# smart_mask_v_2_0.net
KiCad netlist of a schematic drawn in Altium Designer
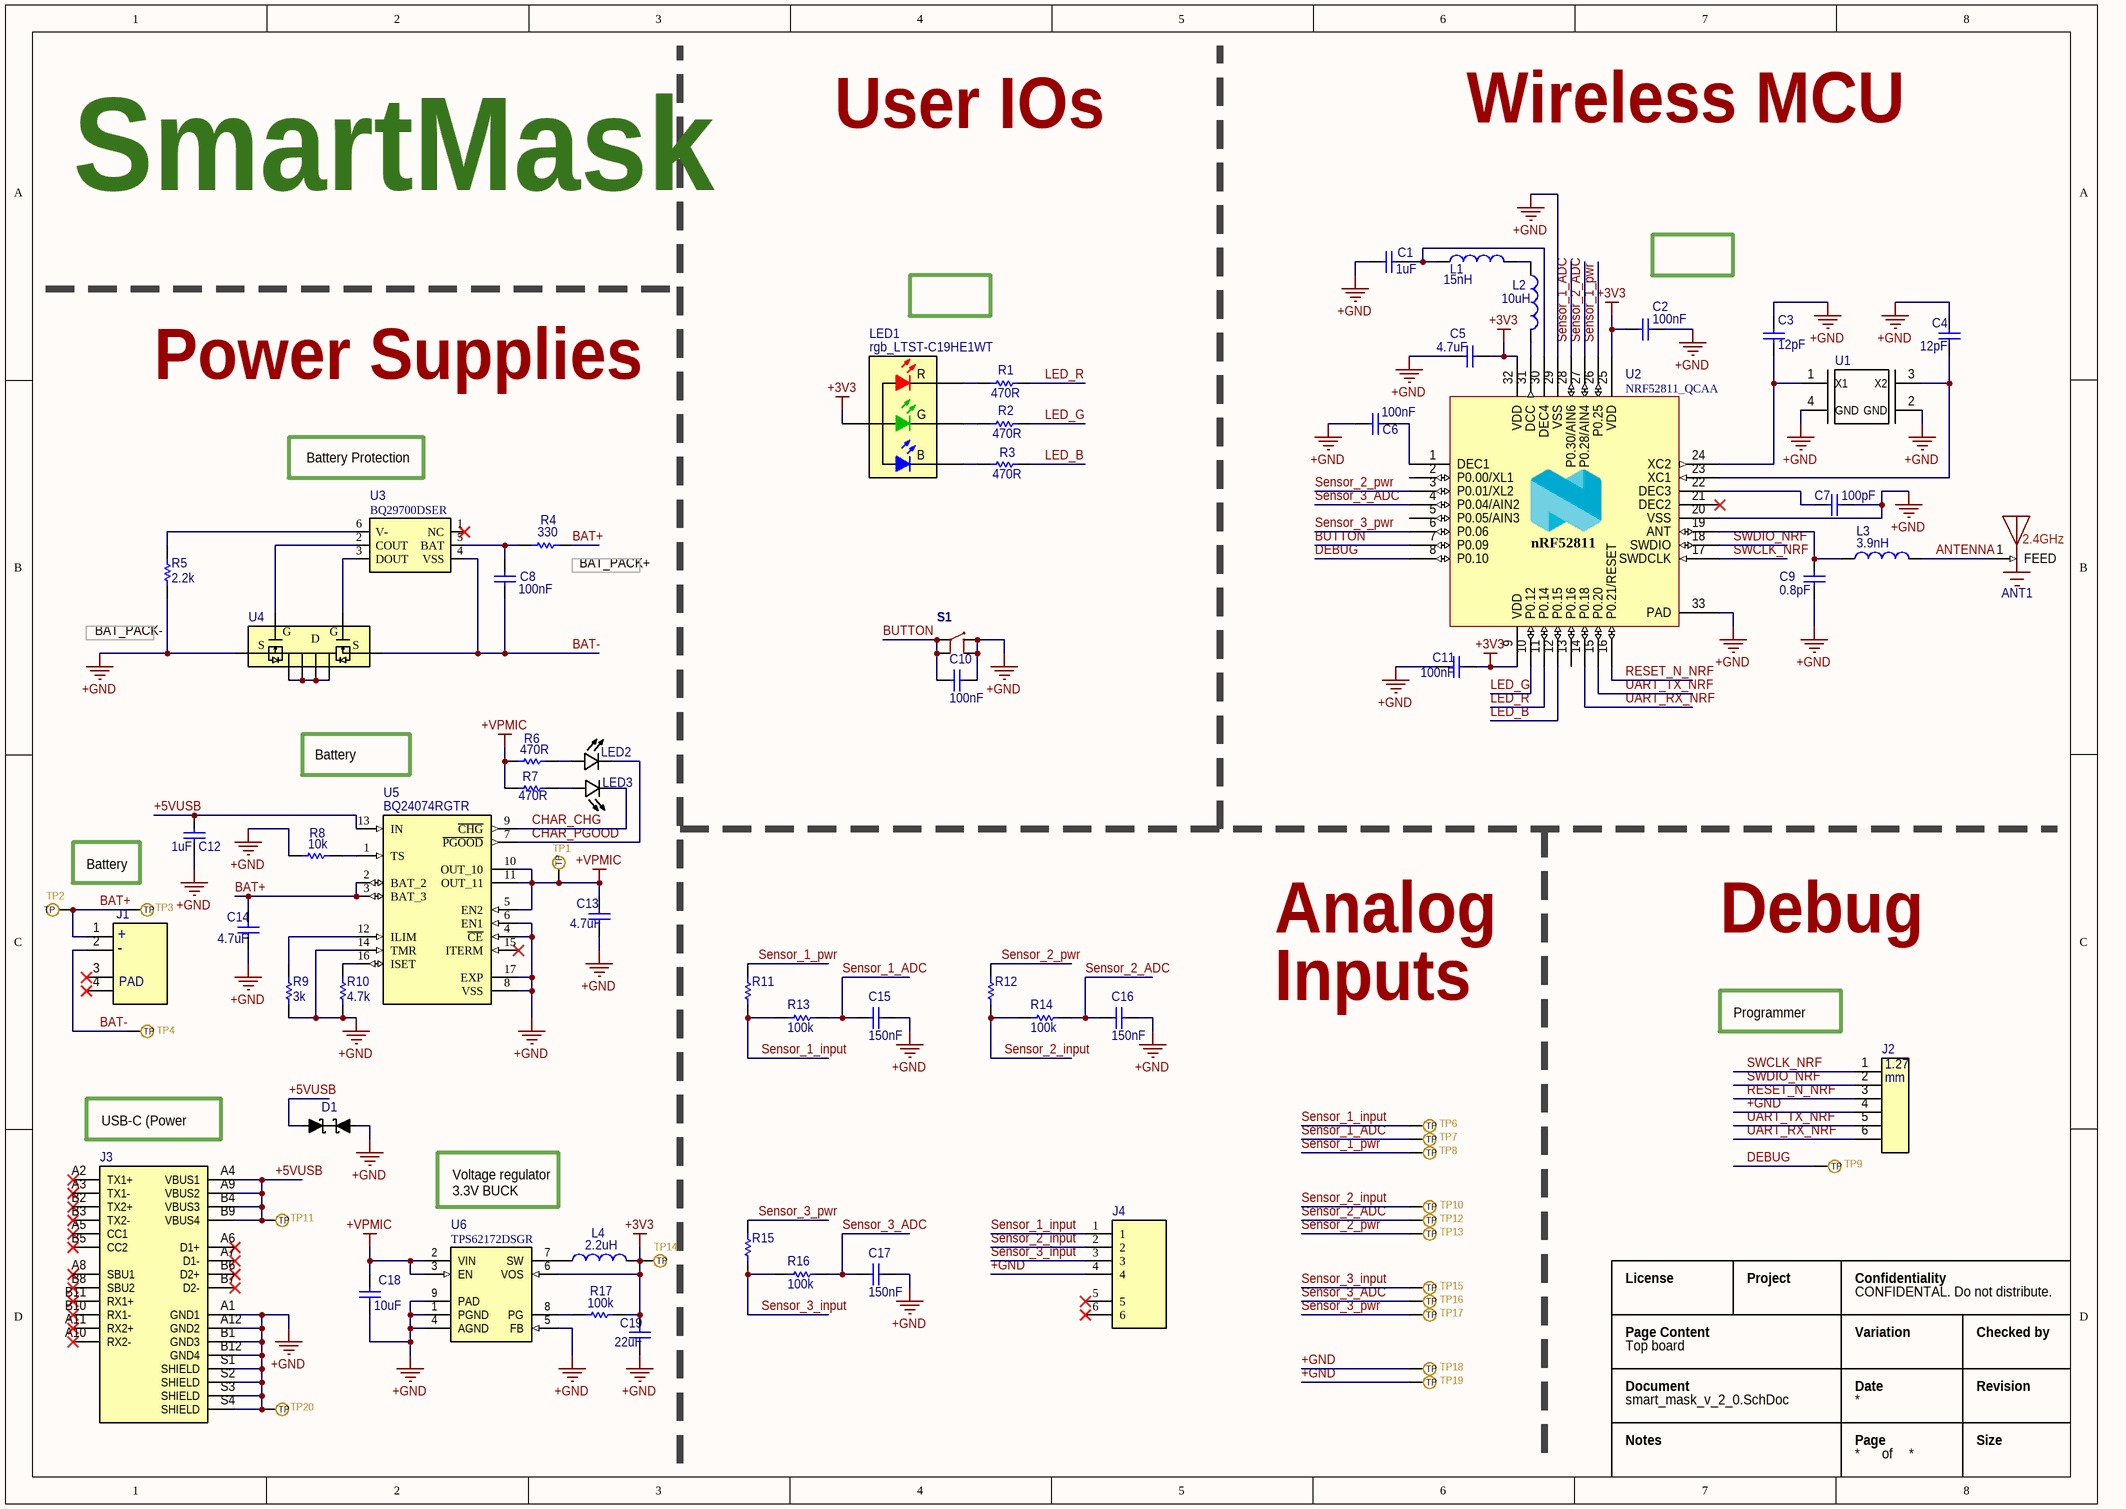
[diagram p0: smart_mask_v_2_0.SchDoc]

(export (version "E")
  (design (tool "Eeschema 10.0.6"))
  (components
    (comp (ref "ANT1")
      (value "2450AT43F0100E")
      (footprint "ANT_2450AT43F0100E")
      (description "RF ANT 2.4GHZ CHIP SOLDER SMD")
      (fields (field (name "MANUFACTURER") "Johanson Technology Inc."))
      (libsource (lib "chips") (part "2450AT43F0100E"))
    )
    (comp (ref "C1")
      (value "1uF")
      (footprint "C0603")
      (description "CAP CER 1UF 10V X5R 0603")
      (fields
        (field (name "MANUFACTURER PART NUMBER") "CL10A105KP8NNNC")
        (field (name "MANUFACTURER") "Samsung Electro-Mechanics")
      )
      (libsource (lib "rcl") (part "CAP 1uF 0603"))
    )
    (comp (ref "C2")
      (value "100nF")
      (footprint "C0402")
      (description "CAP CER 0.1UF 16V X7R 0402")
      (fields
        (field (name "MANUFACTURER PART NUMBER") "GRM155R71C104KA88J")
        (field (name "MANUFACTURER") "Murata Electronics")
      )
      (libsource (lib "rcl") (part "CAP 100nF 0402"))
    )
    (comp (ref "C3")
      (value "12pF")
      (footprint "C0402")
      (description "CAP CER 12PF 50V C0G/NP0 0402")
      (fields
        (field (name "MANUFACTURER PART NUMBER") "GRM1555C1H120JA01J")
        (field (name "MANUFACTURER") "Murata Electronics")
      )
      (libsource (lib "rcl") (part "CAP 12pF 0402"))
    )
    (comp (ref "C4")
      (value "12pF")
      (footprint "C0402")
      (description "CAP CER 12PF 50V C0G/NP0 0402")
      (fields
        (field (name "MANUFACTURER PART NUMBER") "GRM1555C1H120JA01J")
        (field (name "MANUFACTURER") "Murata Electronics")
      )
      (libsource (lib "rcl") (part "CAP 12pF 0402"))
    )
    (comp (ref "C5")
      (value "4.7uF")
      (footprint "C0603")
      (description "CAP CER 4.7UF 10V X5R 0603")
      (fields
        (field (name "MANUFACTURER PART NUMBER") "CL10A475KP8NNNC")
        (field (name "MANUFACTURER") "Samsung Electro-Mechanics")
      )
      (libsource (lib "rcl") (part "CAP 4.7uF 0603"))
    )
    (comp (ref "C6")
      (value "100nF")
      (footprint "C0402")
      (description "CAP CER 0.1UF 16V X7R 0402")
      (fields
        (field (name "MANUFACTURER PART NUMBER") "GRM155R71C104KA88J")
        (field (name "MANUFACTURER") "Murata Electronics")
      )
      (libsource (lib "rcl") (part "CAP 100nF 0402"))
    )
    (comp (ref "C7")
      (value "100pF")
      (footprint "C0402")
      (description "CAP CER 100PF 50V C0G/NP0 0402")
      (fields
        (field (name "MANUFACTURER PART NUMBER") "GRM1555C1H101JA01J")
        (field (name "MANUFACTURER") "Murata Electronics")
      )
      (libsource (lib "rcl") (part "CAP 100pF 0402"))
    )
    (comp (ref "C8")
      (value "100nF")
      (footprint "C0402")
      (description "CAP CER 0.1UF 16V X7R 0402")
      (fields
        (field (name "MANUFACTURER PART NUMBER") "GRM155R71C104KA88J")
        (field (name "MANUFACTURER") "Murata Electronics")
      )
      (libsource (lib "rcl") (part "CAP 100nF 0402"))
    )
    (comp (ref "C9")
      (value "0.8pF")
      (footprint "C0402")
      (description "CAP CER 0.8PF 50V C0G/NP0 0402")
      (fields
        (field (name "MANUFACTURER PART NUMBER") "GRM1555C1HR80BA01J")
        (field (name "MANUFACTURER") "Murata Electronics")
      )
      (libsource (lib "rcl") (part "CAP 0.8pF 0402"))
    )
    (comp (ref "C10")
      (value "100nF")
      (footprint "C0402")
      (description "CAP CER 0.1UF 16V X7R 0402")
      (fields
        (field (name "MANUFACTURER PART NUMBER") "GRM155R71C104KA88J")
        (field (name "MANUFACTURER") "Murata Electronics")
      )
      (libsource (lib "rcl") (part "CAP 100nF 0402"))
    )
    (comp (ref "C11")
      (value "100nF")
      (footprint "C0402")
      (description "CAP CER 0.1UF 16V X7R 0402")
      (fields
        (field (name "MANUFACTURER PART NUMBER") "GRM155R71C104KA88J")
        (field (name "MANUFACTURER") "Murata Electronics")
      )
      (libsource (lib "rcl") (part "CAP 100nF 0402"))
    )
    (comp (ref "C12")
      (value "1uF")
      (footprint "C0402")
      (description "CAP CER 1UF 10V X6S 0402")
      (fields
        (field (name "MANUFACTURER PART NUMBER") "GRM155C81A105KA12D")
        (field (name "MANUFACTURER") "Murata Electronics")
      )
      (libsource (lib "rcl") (part "CAP 1uF 0402"))
    )
    (comp (ref "C13")
      (value "4.7uF")
      (footprint "C0402")
      (description "CAP CER 4.7UF 6.3V X5R 0402")
      (fields
        (field (name "MANUFACTURER PART NUMBER") "GRM155R60J475ME47D")
        (field (name "MANUFACTURER") "Murata Electronics")
      )
      (libsource (lib "rcl") (part "CAP 4.7uF 0402"))
    )
    (comp (ref "C14")
      (value "4.7uF")
      (footprint "C0402")
      (description "CAP CER 4.7UF 6.3V X5R 0402")
      (fields
        (field (name "MANUFACTURER PART NUMBER") "GRM155R60J475ME47D")
        (field (name "MANUFACTURER") "Murata Electronics")
      )
      (libsource (lib "rcl") (part "CAP 4.7uF 0402"))
    )
    (comp (ref "C15")
      (value "150nF")
      (footprint "C0402")
      (description "CAP CER 150nF 16V X7R 0402")
      (fields
        (field (name "MANUFACTURER PART NUMBER") "GRM155R60J154KE01D")
        (field (name "MANUFACTURER") "Murata Electronics")
      )
      (libsource (lib "rcl") (part "CAP 150nF 0402"))
    )
    (comp (ref "C16")
      (value "150nF")
      (footprint "C0402")
      (description "CAP CER 150nF 16V X7R 0402")
      (fields
        (field (name "MANUFACTURER PART NUMBER") "GRM155R60J154KE01D")
        (field (name "MANUFACTURER") "Murata Electronics")
      )
      (libsource (lib "rcl") (part "CAP 150nF 0402"))
    )
    (comp (ref "C17")
      (value "150nF")
      (footprint "C0402")
      (description "CAP CER 150nF 16V X7R 0402")
      (fields
        (field (name "MANUFACTURER PART NUMBER") "GRM155R60J154KE01D")
        (field (name "MANUFACTURER") "Murata Electronics")
      )
      (libsource (lib "rcl") (part "CAP 150nF 0402"))
    )
    (comp (ref "C18")
      (value "10uF")
      (footprint "C0402")
      (description "CAP CER 10UF 4V X5R 0402")
      (fields
        (field (name "MANUFACTURER PART NUMBER") "GRM155R60G106ME44D")
        (field (name "MANUFACTURER") "Murata Electronics")
      )
      (libsource (lib "rcl") (part "CAP 10uF 0402"))
    )
    (comp (ref "C19")
      (value "22uF")
      (footprint "C0603")
      (description "CAP CER 22UF 6.3V X5R 0603")
      (fields
        (field (name "MANUFACTURER PART NUMBER") "GRM188R60J226MEA0D")
        (field (name "MANUFACTURER") "Murata Electronics")
      )
      (libsource (lib "rcl") (part "CAP 22uF 0603"))
    )
    (comp (ref "D1")
      (value "ESD9B5.0ST5G")
      (footprint "Diode_ESD9B5.0ST5G")
      (description "TVS DIODE 5V SOD923")
      (fields (field (name "MANUFACTURER") "ON Semiconductor"))
      (libsource (lib "chips") (part "ESD9B5.0ST5G"))
    )
    (comp (ref "J1")
      (value "0532610271")
      (footprint "0532610271")
      (description "JST Picoblade CONN HEADER SMD R/A 2POS 1.25MM")
      (fields (field (name "MANUFACTURER") "Molex"))
      (libsource (lib "connectors") (part "0532610271"))
    )
    (comp (ref "J2")
      (value "FTS-103-01-F-DV-TR")
      (footprint "CON_6_2_1.27_FTS_103_01")
      (description "CONN HEADER SMD 6POS 1.27MM")
      (fields (field (name "MANUFACTURER") "Samtec Inc."))
      (libsource (lib "connectors") (part "FTS-103-01-F-DV-TR"))
    )
    (comp (ref "J3")
      (value "1054500101")
      (footprint "USB-C-1054500101")
      (description "USB-C CONN RCP USB3.1 TYPEC 24P SMD RA")
      (fields (field (name "MANUFACTURER") "Molex"))
      (libsource (lib "connectors") (part "1054500101"))
    )
    (comp (ref "J4")
      (value "SFW4R-2STE1LF")
      (footprint "SFW4R-2STE1LF")
      (description "CONN FFC FPC TOP 4POS 1.00MM R/A")
      (fields (field (name "MANUFACTURER") "Amphenol ICC (FCI)"))
      (libsource (lib "connectors") (part "SFW4R-2STE1LF"))
    )
    (comp (ref "L1")
      (value "15nH")
      (footprint "L0402")
      (description "FIXED IND 15NH 450MA 320 MOHM")
      (fields
        (field (name "MANUFACTURER") "Murata Electronics")
        (field (name "MANUFACTURER PART NUMBER") "LQG15HS15NJ02D")
      )
      (libsource (lib "rcl") (part "IND 15nH 0402"))
    )
    (comp (ref "L2")
      (value "10uH")
      (footprint "L0603")
      (description "FIXED IND 10UH 50MA 900 MOHM SMD")
      (fields
        (field (name "MANUFACTURER") "Murata Electronics")
        (field (name "MANUFACTURER PART NUMBER") "LQM18FN100M00D")
      )
      (libsource (lib "rcl") (part "IND 10uH 0603"))
    )
    (comp (ref "L3")
      (value "3.9nH")
      (footprint "L0402")
      (description "FIXED IND 3.9NH 750MA 180 MOHM")
      (fields
        (field (name "MANUFACTURER") "Murata Electronics")
        (field (name "MANUFACTURER PART NUMBER") "LQG15HS3N9S02D")
      )
      (libsource (lib "rcl") (part "IND 3.9nH 0402"))
    )
    (comp (ref "L4")
      (value "2.2uH")
      (footprint "L0603")
      (description "2.2UH20% 1.05A(MAX) / 1.15A(TYP.")
      (fields
        (field (name "MANUFACTURER") "Murata Electronics")
        (field (name "MANUFACTURER PART NUMBER") "LQM18PN2R2MGHD")
      )
      (libsource (lib "rcl") (part "IND 2.2uH 0603"))
    )
    (comp (ref "LED1")
      (value "rgb_LTST-C19HE1WT")
      (footprint "LTST-C19HE1WT-4_V")
      (fields
        (field (name "MANUFACTURER") "Lite-On Inc.")
        (field (name "MANUFACTURER PART NUMBER") "LTST-C19HE1WT")
      )
      (libsource (lib "chips") (part "rgb_LTST-C19HE1WT"))
    )
    (comp (ref "LED2")
      (value "LTST-C190CKT")
      (footprint "LTST-C190CKT")
      (description "LED RED CLEAR CHIP SMD")
      (fields (field (name "MANUFACTURER") "Lite-On Inc."))
      (libsource (lib "chips") (part "LTST-C190CKT"))
    )
    (comp (ref "LED3")
      (value "LTST-C190CKT")
      (footprint "LTST-C190CKT")
      (description "LED RED CLEAR CHIP SMD")
      (fields (field (name "MANUFACTURER") "Lite-On Inc."))
      (libsource (lib "chips") (part "LTST-C190CKT"))
    )
    (comp (ref "R1")
      (value "470R")
      (footprint "R0402")
      (description "RES SMD 470 OHM 1% 1/16W 0402")
      (fields
        (field (name "MANUFACTURER") "Yageo")
        (field (name "MANUFACTURER PART NUMBER") "RC0402FR-07470RL")
      )
      (libsource (lib "rcl") (part "RES 470R 0402"))
    )
    (comp (ref "R2")
      (value "470R")
      (footprint "R0402")
      (description "RES SMD 470 OHM 1% 1/16W 0402")
      (fields
        (field (name "MANUFACTURER") "Yageo")
        (field (name "MANUFACTURER PART NUMBER") "RC0402FR-07470RL")
      )
      (libsource (lib "rcl") (part "RES 470R 0402"))
    )
    (comp (ref "R3")
      (value "470R")
      (footprint "R0402")
      (description "RES SMD 470 OHM 1% 1/16W 0402")
      (fields
        (field (name "MANUFACTURER") "Yageo")
        (field (name "MANUFACTURER PART NUMBER") "RC0402FR-07470RL")
      )
      (libsource (lib "rcl") (part "RES 470R 0402"))
    )
    (comp (ref "R4")
      (value "330")
      (footprint "R0402")
      (description "RES SMD 330 OHM 1% 1/16W 0402")
      (fields
        (field (name "MANUFACTURER") "Yageo")
        (field (name "MANUFACTURER PART NUMBER") "RC0402FR-07330RL")
      )
      (libsource (lib "rcl") (part "RES 330R 0402"))
    )
    (comp (ref "R5")
      (value "2.2k")
      (footprint "R0402")
      (description "RES SMD 2.2K OHM 1% 1/16W 0402")
      (fields
        (field (name "MANUFACTURER") "Yageo")
        (field (name "MANUFACTURER PART NUMBER") "RC0402FR-072K2L")
      )
      (libsource (lib "rcl") (part "RES 2.2k 0402"))
    )
    (comp (ref "R6")
      (value "470R")
      (footprint "R0402")
      (description "RES SMD 470 OHM 1% 1/16W 0402")
      (fields
        (field (name "MANUFACTURER") "Yageo")
        (field (name "MANUFACTURER PART NUMBER") "RC0402FR-07470RL")
      )
      (libsource (lib "rcl") (part "RES 470R 0402"))
    )
    (comp (ref "R7")
      (value "470R")
      (footprint "R0402")
      (description "RES SMD 470 OHM 1% 1/16W 0402")
      (fields
        (field (name "MANUFACTURER") "Yageo")
        (field (name "MANUFACTURER PART NUMBER") "RC0402FR-07470RL")
      )
      (libsource (lib "rcl") (part "RES 470R 0402"))
    )
    (comp (ref "R8")
      (value "10k")
      (footprint "R0402")
      (description "RES SMD 10K OHM 1% 1/16W 0402")
      (fields
        (field (name "MANUFACTURER") "Yageo")
        (field (name "MANUFACTURER PART NUMBER") "RC0402FR-0710KL")
      )
      (libsource (lib "rcl") (part "RES 10k 0402"))
    )
    (comp (ref "R9")
      (value "3k")
      (footprint "R0402")
      (description "RES SMD 10K OHM 1% 1/16W 0402")
      (fields
        (field (name "MANUFACTURER") "Yageo")
        (field (name "MANUFACTURER PART NUMBER") "RC0402FR-073KL")
      )
      (libsource (lib "rcl") (part "RES 3k 0402"))
    )
    (comp (ref "R10")
      (value "4.7k")
      (footprint "R0402")
      (description "RES SMD 4.7K OHM 1% 1/16W 0402")
      (fields
        (field (name "MANUFACTURER") "Yageo")
        (field (name "MANUFACTURER PART NUMBER") "RT0402FRE074K7L")
      )
      (libsource (lib "rcl") (part "RES 4.7k 0402"))
    )
    (comp (ref "R11")
      (value "Thick Film")
      (footprint "R0402_DNI")
      (description "DNI (Do Not Install)")
      (libsource (lib "rcl") (part "RES DNI 0402"))
    )
    (comp (ref "R12")
      (value "Thick Film")
      (footprint "R0402_DNI")
      (description "DNI (Do Not Install)")
      (libsource (lib "rcl") (part "RES DNI 0402"))
    )
    (comp (ref "R13")
      (value "100k")
      (footprint "R0402")
      (description "RES SMD 100K OHM 1% 1/16W 0402")
      (fields
        (field (name "MANUFACTURER") "Yageo")
        (field (name "MANUFACTURER PART NUMBER") "RC0402FR-07100KL")
      )
      (libsource (lib "rcl") (part "RES 100k 0402"))
    )
    (comp (ref "R14")
      (value "100k")
      (footprint "R0402")
      (description "RES SMD 100K OHM 1% 1/16W 0402")
      (fields
        (field (name "MANUFACTURER") "Yageo")
        (field (name "MANUFACTURER PART NUMBER") "RC0402FR-07100KL")
      )
      (libsource (lib "rcl") (part "RES 100k 0402"))
    )
    (comp (ref "R15")
      (value "Thick Film")
      (footprint "R0402_DNI")
      (description "DNI (Do Not Install)")
      (libsource (lib "rcl") (part "RES DNI 0402"))
    )
    (comp (ref "R16")
      (value "100k")
      (footprint "R0402")
      (description "RES SMD 100K OHM 1% 1/16W 0402")
      (fields
        (field (name "MANUFACTURER") "Yageo")
        (field (name "MANUFACTURER PART NUMBER") "RC0402FR-07100KL")
      )
      (libsource (lib "rcl") (part "RES 100k 0402"))
    )
    (comp (ref "R17")
      (value "100k")
      (footprint "R0402")
      (description "RES SMD 100K OHM 1% 1/16W 0402")
      (fields
        (field (name "MANUFACTURER") "Yageo")
        (field (name "MANUFACTURER PART NUMBER") "RC0402FR-07100KL")
      )
      (libsource (lib "rcl") (part "RES 100k 0402"))
    )
    (comp (ref "S1")
      (value "EVP-BB2A9B000")
      (footprint "BUTTON_EVP-BB2A9B000")
      (description "SWITCH TACTILE SPST-NO 0.02A 15V")
      (fields (field (name "MANUFACTURER") "Panasonic Electronic Components"))
      (libsource (lib "miscellaneaous") (part "EVP-BB2A9B000"))
    )
    (comp (ref "TP1")
      (value "TP_1mm")
      (footprint "TP_1mm")
      (description "Test point 1mm diameter")
      (libsource (lib "miscellaneaous") (part "TP_1mm"))
    )
    (comp (ref "TP2")
      (value "TP_3mm")
      (footprint "TP_3mm")
      (description "Test point 2mm diameter")
      (libsource (lib "miscellaneaous") (part "TP_3mm"))
    )
    (comp (ref "TP3")
      (value "TP_1mm")
      (footprint "TP_1mm")
      (description "Test point 1mm diameter")
      (libsource (lib "miscellaneaous") (part "TP_1mm"))
    )
    (comp (ref "TP4")
      (value "TP_1mm")
      (footprint "TP_1mm")
      (description "Test point 1mm diameter")
      (libsource (lib "miscellaneaous") (part "TP_1mm"))
    )
    (comp (ref "TP6")
      (value "TP_1mm")
      (footprint "TP_1mm")
      (description "Test point 1mm diameter")
      (libsource (lib "miscellaneaous") (part "TP_1mm"))
    )
    (comp (ref "TP7")
      (value "TP_1mm")
      (footprint "TP_1mm")
      (description "Test point 1mm diameter")
      (libsource (lib "miscellaneaous") (part "TP_1mm"))
    )
    (comp (ref "TP8")
      (value "TP_1mm")
      (footprint "TP_1mm")
      (description "Test point 1mm diameter")
      (libsource (lib "miscellaneaous") (part "TP_1mm"))
    )
    (comp (ref "TP9")
      (value "TP_1mm")
      (footprint "TP_1mm")
      (description "Test point 1mm diameter")
      (libsource (lib "miscellaneaous") (part "TP_1mm"))
    )
    (comp (ref "TP10")
      (value "TP_1mm")
      (footprint "TP_1mm")
      (description "Test point 1mm diameter")
      (libsource (lib "miscellaneaous") (part "TP_1mm"))
    )
    (comp (ref "TP11")
      (value "TP_1mm")
      (footprint "TP_1mm")
      (description "Test point 1mm diameter")
      (libsource (lib "miscellaneaous") (part "TP_1mm"))
    )
    (comp (ref "TP12")
      (value "TP_1mm")
      (footprint "TP_1mm")
      (description "Test point 1mm diameter")
      (libsource (lib "miscellaneaous") (part "TP_1mm"))
    )
    (comp (ref "TP13")
      (value "TP_1mm")
      (footprint "TP_1mm")
      (description "Test point 1mm diameter")
      (libsource (lib "miscellaneaous") (part "TP_1mm"))
    )
    (comp (ref "TP14")
      (value "TP_1mm")
      (footprint "TP_1mm")
      (description "Test point 1mm diameter")
      (libsource (lib "miscellaneaous") (part "TP_1mm"))
    )
    (comp (ref "TP15")
      (value "TP_1mm")
      (footprint "TP_1mm")
      (description "Test point 1mm diameter")
      (libsource (lib "miscellaneaous") (part "TP_1mm"))
    )
    (comp (ref "TP16")
      (value "TP_1mm")
      (footprint "TP_1mm")
      (description "Test point 1mm diameter")
      (libsource (lib "miscellaneaous") (part "TP_1mm"))
    )
    (comp (ref "TP17")
      (value "TP_1mm")
      (footprint "TP_1mm")
      (description "Test point 1mm diameter")
      (libsource (lib "miscellaneaous") (part "TP_1mm"))
    )
    (comp (ref "TP18")
      (value "TP_1mm")
      (footprint "TP_1mm")
      (description "Test point 1mm diameter")
      (libsource (lib "miscellaneaous") (part "TP_1mm"))
    )
    (comp (ref "TP19")
      (value "TP_1mm")
      (footprint "TP_1mm")
      (description "Test point 1mm diameter")
      (libsource (lib "miscellaneaous") (part "TP_1mm"))
    )
    (comp (ref "TP20")
      (value "TP_1mm")
      (footprint "TP_1mm")
      (description "Test point 1mm diameter")
      (libsource (lib "miscellaneaous") (part "TP_1mm"))
    )
    (comp (ref "U1")
      (value "ABM11W-32.0000MHZ-8-B1U-T3")
      (footprint "XTAL_32MHz_ABM11W-32.0000MHZ-8-B1U-T3")
      (description "CRYSTAL 32.0000MHZ 8PF SMD")
      (fields (field (name "MANUFACTURER") "Abracon LLC"))
      (libsource (lib "miscellaneaous") (part "ABM11W-32.0000MHZ-8-B1U-T3"))
    )
    (comp (ref "U2")
      (value "NRF52811_QCAA")
      (footprint "NRF52811_QCAA")
      (description "NRF52811 Nordic Bluetooth 5.1 chip 32 pins QFN32")
      (fields
        (field (name "MANUFACTURER") "Nordic Semiconductor")
        (field (name "MANUFACTURER PART NUMBER") "949-NRF52811-QCAA-R")
      )
      (libsource (lib "chips") (part "NRF52811_QCAA"))
    )
    (comp (ref "U3")
      (value "BQ29700DSER")
      (footprint "BATT_PROTEC_BQ29700DSER")
      (description "BATT LITHIUM BATT PROTECT 6-SON")
      (fields (field (name "MANUFACTURER") "Texas Instruments"))
      (libsource (lib "chips") (part "BQ29700DSER"))
    )
    (comp (ref "U4")
      (value "ECH8693R-TL-W")
      (footprint "MOSFET_2CHAN_ECH8693R-TL-W")
      (description "MOSFET 2N-CH 24V 14A SOT-28")
      (fields (field (name "MANUFACTURER") "ON Semiconductor"))
      (libsource (lib "chips") (part "ECH8693R-TL-W"))
    )
    (comp (ref "U5")
      (value "BQ24074RGTR")
      (footprint "BATT_CHARG_BQ24074RGTR")
      (description "BATT LI-ION CHARGE MGMT 16-QFN")
      (fields
        (field (name "MANUFACTURER") "Texas Instruments")
        (field (name "MANUFACTURER PART NUMBER") "BQ24074RGTR")
      )
      (libsource (lib "chips") (part "BQ24074RGTR"))
    )
    (comp (ref "U6")
      (value "TPS62172DSGR")
      (footprint "REG_BUCK_TPS62172DSGR")
      (description "REG BUCK 3.3V 500MA 8WSON")
      (fields (field (name "MANUFACTURER") "Texas Instruments"))
      (libsource (lib "chips") (part "TPS62172DSGR"))
    )
  )
  (nets
    (net (code "1") (name "+3V3") (class "Default")
      (node (ref "C11") (pin "1") (pinfunction "1_1") (pintype "passive"))
      (node (ref "C19") (pin "2") (pinfunction "2_2") (pintype "passive"))
      (node (ref "C2") (pin "2") (pinfunction "2_2") (pintype "passive"))
      (node (ref "C5") (pin "1") (pinfunction "1_1") (pintype "passive"))
      (node (ref "L4") (pin "2") (pinfunction "2_2") (pintype "passive"))
      (node (ref "LED1") (pin "4") (pinfunction "A_4") (pintype "passive"))
      (node (ref "R17") (pin "2") (pinfunction "2_2") (pintype "passive"))
      (node (ref "TP14") (pin "1") (pinfunction "TP_1") (pintype "passive"))
      (node (ref "U2") (pin "25") (pinfunction "VDD_25") (pintype "power_in"))
      (node (ref "U2") (pin "32") (pinfunction "VDD_32") (pintype "power_in"))
      (node (ref "U2") (pin "9") (pinfunction "VDD_9") (pintype "power_in"))
      (node (ref "U6") (pin "6") (pinfunction "VOS_6") (pintype "input"))
    )
    (net (code "2") (name "+GND") (class "Default")
      (node (ref "C1") (pin "1") (pinfunction "1_1") (pintype "passive"))
      (node (ref "C10") (pin "1") (pinfunction "1_1") (pintype "passive"))
      (node (ref "C11") (pin "2") (pinfunction "2_2") (pintype "passive"))
      (node (ref "C12") (pin "1") (pinfunction "1_1") (pintype "passive"))
      (node (ref "C13") (pin "1") (pinfunction "1_1") (pintype "passive"))
      (node (ref "C14") (pin "1") (pinfunction "1_1") (pintype "passive"))
      (node (ref "C15") (pin "2") (pinfunction "2_2") (pintype "passive"))
      (node (ref "C16") (pin "2") (pinfunction "2_2") (pintype "passive"))
      (node (ref "C17") (pin "2") (pinfunction "2_2") (pintype "passive"))
      (node (ref "C18") (pin "1") (pinfunction "1_1") (pintype "passive"))
      (node (ref "C19") (pin "1") (pinfunction "1_1") (pintype "passive"))
      (node (ref "C2") (pin "1") (pinfunction "1_1") (pintype "passive"))
      (node (ref "C3") (pin "2") (pinfunction "2_2") (pintype "passive"))
      (node (ref "C4") (pin "2") (pinfunction "2_2") (pintype "passive"))
      (node (ref "C5") (pin "2") (pinfunction "2_2") (pintype "passive"))
      (node (ref "C6") (pin "2") (pinfunction "2_2") (pintype "passive"))
      (node (ref "C7") (pin "2") (pinfunction "2_2") (pintype "passive"))
      (node (ref "C9") (pin "1") (pinfunction "1_1") (pintype "passive"))
      (node (ref "D1") (pin "1") (pinfunction "1_1") (pintype "passive"))
      (node (ref "J2") (pin "4") (pinfunction "4_4") (pintype "passive"))
      (node (ref "J3") (pin "A1") (pinfunction "GND1_A1") (pintype "passive"))
      (node (ref "J3") (pin "A12") (pinfunction "GND2_A12") (pintype "passive"))
      (node (ref "J3") (pin "B1") (pinfunction "GND3_B1") (pintype "passive"))
      (node (ref "J3") (pin "B12") (pinfunction "GND4_B12") (pintype "passive"))
      (node (ref "J3") (pin "S1") (pinfunction "SHIELD_S1") (pintype "passive"))
      (node (ref "J3") (pin "S2") (pinfunction "SHIELD_S2") (pintype "passive"))
      (node (ref "J3") (pin "S3") (pinfunction "SHIELD_S3") (pintype "passive"))
      (node (ref "J3") (pin "S4") (pinfunction "SHIELD_S4") (pintype "passive"))
      (node (ref "J4") (pin "4") (pinfunction "4_4") (pintype "passive"))
      (node (ref "R10") (pin "1") (pinfunction "1_1") (pintype "passive"))
      (node (ref "R5") (pin "1") (pinfunction "1_1") (pintype "passive"))
      (node (ref "R8") (pin "2") (pinfunction "2_2") (pintype "passive"))
      (node (ref "R9") (pin "1") (pinfunction "1_1") (pintype "passive"))
      (node (ref "S1") (pin "B1") (pinfunction "B1_B1") (pintype "passive"))
      (node (ref "S1") (pin "B2") (pinfunction "B2_B2") (pintype "passive"))
      (node (ref "TP18") (pin "1") (pinfunction "TP_1") (pintype "passive"))
      (node (ref "TP19") (pin "1") (pinfunction "TP_1") (pintype "passive"))
      (node (ref "TP20") (pin "1") (pinfunction "TP_1") (pintype "passive"))
      (node (ref "U1") (pin "2") (pinfunction "GND_2") (pintype "passive"))
      (node (ref "U1") (pin "4") (pinfunction "GND_4") (pintype "passive"))
      (node (ref "U2") (pin "20") (pinfunction "VSS_20") (pintype "power_in"))
      (node (ref "U2") (pin "29") (pinfunction "VSS_29") (pintype "power_in"))
      (node (ref "U2") (pin "33") (pinfunction "PAD_33") (pintype "power_in"))
      (node (ref "U4") (pin "1") (pinfunction "S1_1") (pintype "passive"))
      (node (ref "U5") (pin "14") (pinfunction "TMR_14") (pintype "input"))
      (node (ref "U5") (pin "17") (pinfunction "EXP_17") (pintype "power_in"))
      (node (ref "U5") (pin "4") (pinfunction "~{CE}_4") (pintype "input"))
      (node (ref "U5") (pin "6") (pinfunction "EN1_6") (pintype "input"))
      (node (ref "U5") (pin "8") (pinfunction "VSS_8") (pintype "power_in"))
      (node (ref "U6") (pin "1") (pinfunction "PGND_1") (pintype "power_in"))
      (node (ref "U6") (pin "4") (pinfunction "AGND_4") (pintype "power_in"))
      (node (ref "U6") (pin "5") (pinfunction "FB_5") (pintype "input"))
      (node (ref "U6") (pin "9") (pinfunction "PAD_9") (pintype "power_in"))
    )
    (net (code "3") (name "+VPMIC") (class "Default")
      (node (ref "C13") (pin "2") (pinfunction "2_2") (pintype "passive"))
      (node (ref "C18") (pin "2") (pinfunction "2_2") (pintype "passive"))
      (node (ref "R6") (pin "2") (pinfunction "2_2") (pintype "passive"))
      (node (ref "R7") (pin "2") (pinfunction "2_2") (pintype "passive"))
      (node (ref "TP1") (pin "1") (pinfunction "TP_1") (pintype "passive"))
      (node (ref "U5") (pin "10") (pinfunction "OUT_10_10") (pintype "power_in"))
      (node (ref "U5") (pin "11") (pinfunction "OUT_11_11") (pintype "power_in"))
      (node (ref "U5") (pin "5") (pinfunction "EN2_5") (pintype "input"))
      (node (ref "U6") (pin "2") (pinfunction "VIN_2") (pintype "power_in"))
      (node (ref "U6") (pin "3") (pinfunction "EN_3") (pintype "input"))
    )
    (net (code "4") (name "/+5VUSB") (class "Default")
      (node (ref "C12") (pin "2") (pinfunction "2_2") (pintype "passive"))
      (node (ref "D1") (pin "2") (pinfunction "2_2") (pintype "passive"))
      (node (ref "J3") (pin "A4") (pinfunction "VBUS1_A4") (pintype "passive"))
      (node (ref "J3") (pin "A9") (pinfunction "VBUS2_A9") (pintype "passive"))
      (node (ref "J3") (pin "B4") (pinfunction "VBUS3_B4") (pintype "passive"))
      (node (ref "J3") (pin "B9") (pinfunction "VBUS4_B9") (pintype "passive"))
      (node (ref "TP11") (pin "1") (pinfunction "TP_1") (pintype "passive"))
      (node (ref "U5") (pin "13") (pinfunction "IN_13") (pintype "input"))
    )
    (net (code "5") (name "/ANTENNA") (class "Default")
      (node (ref "ANT1") (pin "1") (pinfunction "FEED_1") (pintype "input"))
      (node (ref "L3") (pin "2") (pinfunction "2_2") (pintype "passive"))
    )
    (net (code "6") (name "/BAT+") (class "Default")
      (node (ref "C14") (pin "2") (pinfunction "2_2") (pintype "passive"))
      (node (ref "J1") (pin "1") (pinfunction "1_1") (pintype "passive"))
      (node (ref "R4") (pin "2") (pinfunction "2_2") (pintype "passive"))
      (node (ref "TP2") (pin "1") (pinfunction "TP_1") (pintype "passive"))
      (node (ref "TP3") (pin "1") (pinfunction "TP_1") (pintype "passive"))
      (node (ref "U5") (pin "2") (pinfunction "BAT_2_2") (pintype "bidirectional"))
      (node (ref "U5") (pin "3") (pinfunction "BAT_3_3") (pintype "bidirectional"))
    )
    (net (code "7") (name "/BAT-") (class "Default")
      (node (ref "C8") (pin "1") (pinfunction "1_1") (pintype "passive"))
      (node (ref "J1") (pin "2") (pinfunction "2_2") (pintype "passive"))
      (node (ref "TP4") (pin "1") (pinfunction "TP_1") (pintype "passive"))
      (node (ref "U3") (pin "4") (pinfunction "VSS_4") (pintype "passive"))
      (node (ref "U4") (pin "3") (pinfunction "S2_3") (pintype "passive"))
    )
    (net (code "8") (name "/BUTTON") (class "Default")
      (node (ref "C10") (pin "2") (pinfunction "2_2") (pintype "passive"))
      (node (ref "S1") (pin "A1") (pinfunction "A1_A1") (pintype "passive"))
      (node (ref "S1") (pin "A2") (pinfunction "A2_A2") (pintype "passive"))
      (node (ref "U2") (pin "7") (pinfunction "P0.09_7") (pintype "bidirectional"))
    )
    (net (code "9") (name "/CHAR_CHG") (class "Default")
      (node (ref "LED3") (pin "C") (pinfunction "C_C") (pintype "passive"))
      (node (ref "U5") (pin "9") (pinfunction "~{CHG}_9") (pintype "output"))
    )
    (net (code "10") (name "/CHAR_PGOOD") (class "Default")
      (node (ref "LED2") (pin "C") (pinfunction "C_C") (pintype "passive"))
      (node (ref "U5") (pin "7") (pinfunction "~{PGOOD}_7") (pintype "output"))
    )
    (net (code "11") (name "/DEBUG") (class "Default")
      (node (ref "TP9") (pin "1") (pinfunction "TP_1") (pintype "passive"))
      (node (ref "U2") (pin "8") (pinfunction "P0.10_8") (pintype "bidirectional"))
    )
    (net (code "12") (name "/LED_B") (class "Default")
      (node (ref "R3") (pin "2") (pinfunction "2_2") (pintype "passive"))
      (node (ref "U2") (pin "12") (pinfunction "P0.15_12") (pintype "bidirectional"))
    )
    (net (code "13") (name "/LED_G") (class "Default")
      (node (ref "R2") (pin "2") (pinfunction "2_2") (pintype "passive"))
      (node (ref "U2") (pin "10") (pinfunction "P0.12_10") (pintype "bidirectional"))
    )
    (net (code "14") (name "/LED_R") (class "Default")
      (node (ref "R1") (pin "2") (pinfunction "2_2") (pintype "passive"))
      (node (ref "U2") (pin "11") (pinfunction "P0.14_11") (pintype "bidirectional"))
    )
    (net (code "15") (name "/RESET_N_NRF") (class "Default")
      (node (ref "J2") (pin "3") (pinfunction "3_3") (pintype "passive"))
      (node (ref "U2") (pin "16") (pinfunction "P0.21/RESET_16") (pintype "bidirectional"))
    )
    (net (code "16") (name "/SWCLK_NRF") (class "Default")
      (node (ref "J2") (pin "1") (pinfunction "1_1") (pintype "passive"))
      (node (ref "U2") (pin "17") (pinfunction "SWDCLK_17") (pintype "input"))
    )
    (net (code "17") (name "/SWDIO_NRF") (class "Default")
      (node (ref "J2") (pin "2") (pinfunction "2_2") (pintype "passive"))
      (node (ref "U2") (pin "18") (pinfunction "SWDIO_18") (pintype "bidirectional"))
    )
    (net (code "18") (name "/Sensor_1_ADC") (class "Default")
      (node (ref "C15") (pin "1") (pinfunction "1_1") (pintype "passive"))
      (node (ref "R13") (pin "2") (pinfunction "2_2") (pintype "passive"))
      (node (ref "TP7") (pin "1") (pinfunction "TP_1") (pintype "passive"))
      (node (ref "U2") (pin "28") (pinfunction "P0.30/AIN6_28") (pintype "bidirectional"))
    )
    (net (code "19") (name "/Sensor_1_input") (class "Default")
      (node (ref "J4") (pin "1") (pinfunction "1_1") (pintype "passive"))
      (node (ref "R11") (pin "1") (pinfunction "1_1") (pintype "passive"))
      (node (ref "R13") (pin "1") (pinfunction "1_1") (pintype "passive"))
      (node (ref "TP6") (pin "1") (pinfunction "TP_1") (pintype "passive"))
    )
    (net (code "20") (name "/Sensor_1_pwr") (class "Default")
      (node (ref "R11") (pin "2") (pinfunction "2_2") (pintype "passive"))
      (node (ref "TP8") (pin "1") (pinfunction "TP_1") (pintype "passive"))
      (node (ref "U2") (pin "26") (pinfunction "P0.25_26") (pintype "bidirectional"))
    )
    (net (code "21") (name "/Sensor_2_ADC") (class "Default")
      (node (ref "C16") (pin "1") (pinfunction "1_1") (pintype "passive"))
      (node (ref "R14") (pin "2") (pinfunction "2_2") (pintype "passive"))
      (node (ref "TP12") (pin "1") (pinfunction "TP_1") (pintype "passive"))
      (node (ref "U2") (pin "27") (pinfunction "P0.28/AIN4_27") (pintype "bidirectional"))
    )
    (net (code "22") (name "/Sensor_2_input") (class "Default")
      (node (ref "J4") (pin "2") (pinfunction "2_2") (pintype "passive"))
      (node (ref "R12") (pin "1") (pinfunction "1_1") (pintype "passive"))
      (node (ref "R14") (pin "1") (pinfunction "1_1") (pintype "passive"))
      (node (ref "TP10") (pin "1") (pinfunction "TP_1") (pintype "passive"))
    )
    (net (code "23") (name "/Sensor_2_pwr") (class "Default")
      (node (ref "R12") (pin "2") (pinfunction "2_2") (pintype "passive"))
      (node (ref "TP13") (pin "1") (pinfunction "TP_1") (pintype "passive"))
      (node (ref "U2") (pin "3") (pinfunction "P0.01/XL2_3") (pintype "bidirectional"))
    )
    (net (code "24") (name "/Sensor_3_ADC") (class "Default")
      (node (ref "C17") (pin "1") (pinfunction "1_1") (pintype "passive"))
      (node (ref "R16") (pin "2") (pinfunction "2_2") (pintype "passive"))
      (node (ref "TP16") (pin "1") (pinfunction "TP_1") (pintype "passive"))
      (node (ref "U2") (pin "4") (pinfunction "P0.04/AIN2_4") (pintype "bidirectional"))
    )
    (net (code "25") (name "/Sensor_3_input") (class "Default")
      (node (ref "J4") (pin "3") (pinfunction "3_3") (pintype "passive"))
      (node (ref "R15") (pin "1") (pinfunction "1_1") (pintype "passive"))
      (node (ref "R16") (pin "1") (pinfunction "1_1") (pintype "passive"))
      (node (ref "TP15") (pin "1") (pinfunction "TP_1") (pintype "passive"))
    )
    (net (code "26") (name "/Sensor_3_pwr") (class "Default")
      (node (ref "R15") (pin "2") (pinfunction "2_2") (pintype "passive"))
      (node (ref "TP17") (pin "1") (pinfunction "TP_1") (pintype "passive"))
      (node (ref "U2") (pin "6") (pinfunction "P0.06_6") (pintype "bidirectional"))
    )
    (net (code "27") (name "/UART_RX_NRF") (class "Default")
      (node (ref "J2") (pin "6") (pinfunction "6_6") (pintype "passive"))
      (node (ref "U2") (pin "14") (pinfunction "P0.18_14") (pintype "bidirectional"))
    )
    (net (code "28") (name "/UART_TX_NRF") (class "Default")
      (node (ref "J2") (pin "5") (pinfunction "5_5") (pintype "passive"))
      (node (ref "U2") (pin "15") (pinfunction "P0.20_15") (pintype "bidirectional"))
    )
    (net (code "29") (name "Net-(L1-Pad2)") (class "Default")
      (node (ref "L1") (pin "2") (pinfunction "2_2") (pintype "passive"))
      (node (ref "L2") (pin "1") (pinfunction "1_1") (pintype "passive"))
    )
    (net (code "30") (name "Net-(LED1-B)") (class "Default")
      (node (ref "LED1") (pin "3") (pinfunction "B_3") (pintype "passive"))
      (node (ref "R3") (pin "1") (pinfunction "1_1") (pintype "passive"))
    )
    (net (code "31") (name "Net-(LED1-G)") (class "Default")
      (node (ref "LED1") (pin "2") (pinfunction "G_2") (pintype "passive"))
      (node (ref "R2") (pin "1") (pinfunction "1_1") (pintype "passive"))
    )
    (net (code "32") (name "Net-(LED1-R)") (class "Default")
      (node (ref "LED1") (pin "1") (pinfunction "R_1") (pintype "passive"))
      (node (ref "R1") (pin "1") (pinfunction "1_1") (pintype "passive"))
    )
    (net (code "33") (name "Net-(LED2-PadA)") (class "Default")
      (node (ref "LED2") (pin "A") (pinfunction "A_A") (pintype "passive"))
      (node (ref "R6") (pin "1") (pinfunction "1_1") (pintype "passive"))
    )
    (net (code "34") (name "Net-(LED3-PadA)") (class "Default")
      (node (ref "LED3") (pin "A") (pinfunction "A_A") (pintype "passive"))
      (node (ref "R7") (pin "1") (pinfunction "1_1") (pintype "passive"))
    )
    (net (code "35") (name "Net-(U1-X1)") (class "Default")
      (node (ref "C3") (pin "1") (pinfunction "1_1") (pintype "passive"))
      (node (ref "U1") (pin "1") (pinfunction "X1_1") (pintype "passive"))
      (node (ref "U2") (pin "24") (pinfunction "XC2_24") (pintype "output"))
    )
    (net (code "36") (name "Net-(U1-X2)") (class "Default")
      (node (ref "C4") (pin "1") (pinfunction "1_1") (pintype "passive"))
      (node (ref "U1") (pin "3") (pinfunction "X2_3") (pintype "passive"))
      (node (ref "U2") (pin "23") (pinfunction "XC1_23") (pintype "input"))
    )
    (net (code "37") (name "Net-(U2-ANT)") (class "Default")
      (node (ref "C9") (pin "2") (pinfunction "2_2") (pintype "passive"))
      (node (ref "L3") (pin "1") (pinfunction "1_1") (pintype "passive"))
      (node (ref "U2") (pin "19") (pinfunction "ANT_19") (pintype "bidirectional"))
    )
    (net (code "38") (name "Net-(U2-DCC)") (class "Default")
      (node (ref "L2") (pin "2") (pinfunction "2_2") (pintype "passive"))
      (node (ref "U2") (pin "31") (pinfunction "DCC_31") (pintype "output"))
    )
    (net (code "39") (name "Net-(U2-DEC1)") (class "Default")
      (node (ref "C6") (pin "1") (pinfunction "1_1") (pintype "passive"))
      (node (ref "U2") (pin "1") (pinfunction "DEC1_1") (pintype "power_in"))
    )
    (net (code "40") (name "Net-(U2-DEC3)") (class "Default")
      (node (ref "C7") (pin "1") (pinfunction "1_1") (pintype "passive"))
      (node (ref "U2") (pin "22") (pinfunction "DEC3_22") (pintype "power_in"))
    )
    (net (code "41") (name "Net-(U2-DEC4)") (class "Default")
      (node (ref "C1") (pin "2") (pinfunction "2_2") (pintype "passive"))
      (node (ref "L1") (pin "1") (pinfunction "1_1") (pintype "passive"))
      (node (ref "U2") (pin "30") (pinfunction "DEC4_30") (pintype "power_in"))
    )
    (net (code "42") (name "Net-(U3-BAT)") (class "Default")
      (node (ref "C8") (pin "2") (pinfunction "2_2") (pintype "passive"))
      (node (ref "R4") (pin "1") (pinfunction "1_1") (pintype "passive"))
      (node (ref "U3") (pin "5") (pinfunction "BAT_5") (pintype "passive"))
    )
    (net (code "43") (name "Net-(U3-COUT)") (class "Default")
      (node (ref "U3") (pin "2") (pinfunction "COUT_2") (pintype "passive"))
      (node (ref "U4") (pin "2") (pinfunction "G1_2") (pintype "passive"))
    )
    (net (code "44") (name "Net-(U3-DOUT)") (class "Default")
      (node (ref "U3") (pin "3") (pinfunction "DOUT_3") (pintype "passive"))
      (node (ref "U4") (pin "4") (pinfunction "G2_4") (pintype "passive"))
    )
    (net (code "45") (name "Net-(U3-V-)") (class "Default")
      (node (ref "R5") (pin "2") (pinfunction "2_2") (pintype "passive"))
      (node (ref "U3") (pin "6") (pinfunction "V-_6") (pintype "passive"))
    )
    (net (code "46") (name "Net-(U4-D-Pad5)") (class "Default")
      (node (ref "U4") (pin "5") (pinfunction "D_5") (pintype "passive"))
      (node (ref "U4") (pin "6") (pinfunction "D_6") (pintype "passive"))
      (node (ref "U4") (pin "7") (pinfunction "D_7") (pintype "passive"))
      (node (ref "U4") (pin "8") (pinfunction "D_8") (pintype "passive"))
    )
    (net (code "47") (name "Net-(U5-ILIM)") (class "Default")
      (node (ref "R9") (pin "2") (pinfunction "2_2") (pintype "passive"))
      (node (ref "U5") (pin "12") (pinfunction "ILIM_12") (pintype "input"))
    )
    (net (code "48") (name "Net-(U5-ISET)") (class "Default")
      (node (ref "R10") (pin "2") (pinfunction "2_2") (pintype "passive"))
      (node (ref "U5") (pin "16") (pinfunction "ISET_16") (pintype "bidirectional"))
    )
    (net (code "49") (name "Net-(U5-TS)") (class "Default")
      (node (ref "R8") (pin "1") (pinfunction "1_1") (pintype "passive"))
      (node (ref "U5") (pin "1") (pinfunction "TS_1") (pintype "input"))
    )
    (net (code "50") (name "Net-(U6-PG)") (class "Default")
      (node (ref "R17") (pin "1") (pinfunction "1_1") (pintype "passive"))
      (node (ref "U6") (pin "8") (pinfunction "PG_8") (pintype "tri_state"))
    )
    (net (code "51") (name "Net-(U6-SW)") (class "Default")
      (node (ref "L4") (pin "1") (pinfunction "1_1") (pintype "passive"))
      (node (ref "U6") (pin "7") (pinfunction "SW_7") (pintype "power_in"))
    )
    (net (code "52") (name "unconnected-(J1-Pad3)") (class "Default")
      (node (ref "J1") (pin "3") (pinfunction "3_3") (pintype "passive+no_connect"))
    )
    (net (code "53") (name "unconnected-(J1-Pad4)") (class "Default")
      (node (ref "J1") (pin "4") (pinfunction "4_4") (pintype "passive+no_connect"))
    )
    (net (code "54") (name "unconnected-(J3-CC1-PadA5)") (class "Default")
      (node (ref "J3") (pin "A5") (pinfunction "CC1_A5") (pintype "passive+no_connect"))
    )
    (net (code "55") (name "unconnected-(J3-CC2-PadB5)") (class "Default")
      (node (ref "J3") (pin "B5") (pinfunction "CC2_B5") (pintype "passive+no_connect"))
    )
    (net (code "56") (name "unconnected-(J3-D1+-PadA6)") (class "Default")
      (node (ref "J3") (pin "A6") (pinfunction "D1+_A6") (pintype "passive+no_connect"))
    )
    (net (code "57") (name "unconnected-(J3-D1--PadA7)") (class "Default")
      (node (ref "J3") (pin "A7") (pinfunction "D1-_A7") (pintype "passive+no_connect"))
    )
    (net (code "58") (name "unconnected-(J3-D2+-PadB6)") (class "Default")
      (node (ref "J3") (pin "B6") (pinfunction "D2+_B6") (pintype "passive+no_connect"))
    )
    (net (code "59") (name "unconnected-(J3-D2--PadB7)") (class "Default")
      (node (ref "J3") (pin "B7") (pinfunction "D2-_B7") (pintype "passive+no_connect"))
    )
    (net (code "60") (name "unconnected-(J3-RX1+-PadB11)") (class "Default")
      (node (ref "J3") (pin "B11") (pinfunction "RX1+_B11") (pintype "passive+no_connect"))
    )
    (net (code "61") (name "unconnected-(J3-RX1--PadB10)") (class "Default")
      (node (ref "J3") (pin "B10") (pinfunction "RX1-_B10") (pintype "passive+no_connect"))
    )
    (net (code "62") (name "unconnected-(J3-RX2+-PadA11)") (class "Default")
      (node (ref "J3") (pin "A11") (pinfunction "RX2+_A11") (pintype "passive+no_connect"))
    )
    (net (code "63") (name "unconnected-(J3-RX2--PadA10)") (class "Default")
      (node (ref "J3") (pin "A10") (pinfunction "RX2-_A10") (pintype "passive+no_connect"))
    )
    (net (code "64") (name "unconnected-(J3-SBU1-PadA8)") (class "Default")
      (node (ref "J3") (pin "A8") (pinfunction "SBU1_A8") (pintype "passive+no_connect"))
    )
    (net (code "65") (name "unconnected-(J3-SBU2-PadB8)") (class "Default")
      (node (ref "J3") (pin "B8") (pinfunction "SBU2_B8") (pintype "passive+no_connect"))
    )
    (net (code "66") (name "unconnected-(J3-TX1+-PadA2)") (class "Default")
      (node (ref "J3") (pin "A2") (pinfunction "TX1+_A2") (pintype "passive+no_connect"))
    )
    (net (code "67") (name "unconnected-(J3-TX1--PadA3)") (class "Default")
      (node (ref "J3") (pin "A3") (pinfunction "TX1-_A3") (pintype "passive+no_connect"))
    )
    (net (code "68") (name "unconnected-(J3-TX2+-PadB2)") (class "Default")
      (node (ref "J3") (pin "B2") (pinfunction "TX2+_B2") (pintype "passive+no_connect"))
    )
    (net (code "69") (name "unconnected-(J3-TX2--PadB3)") (class "Default")
      (node (ref "J3") (pin "B3") (pinfunction "TX2-_B3") (pintype "passive+no_connect"))
    )
    (net (code "70") (name "unconnected-(J4-Pad5)") (class "Default")
      (node (ref "J4") (pin "5") (pinfunction "5_5") (pintype "passive+no_connect"))
    )
    (net (code "71") (name "unconnected-(J4-Pad6)") (class "Default")
      (node (ref "J4") (pin "6") (pinfunction "6_6") (pintype "passive+no_connect"))
    )
    (net (code "72") (name "unconnected-(U2-DEC2-Pad21)") (class "Default")
      (node (ref "U2") (pin "21") (pinfunction "DEC2_21") (pintype "power_in+no_connect"))
    )
    (net (code "73") (name "unconnected-(U2-P0.00{slash}XL1-Pad2)") (class "Default")
      (node (ref "U2") (pin "2") (pinfunction "P0.00/XL1_2") (pintype "bidirectional"))
    )
    (net (code "74") (name "unconnected-(U2-P0.05{slash}AIN3-Pad5)") (class "Default")
      (node (ref "U2") (pin "5") (pinfunction "P0.05/AIN3_5") (pintype "bidirectional"))
    )
    (net (code "75") (name "unconnected-(U2-P0.16-Pad13)") (class "Default")
      (node (ref "U2") (pin "13") (pinfunction "P0.16_13") (pintype "bidirectional"))
    )
    (net (code "76") (name "unconnected-(U3-NC-Pad1)") (class "Default")
      (node (ref "U3") (pin "1") (pinfunction "NC_1") (pintype "passive+no_connect"))
    )
    (net (code "77") (name "unconnected-(U5-ITERM-Pad15)") (class "Default")
      (node (ref "U5") (pin "15") (pinfunction "ITERM_15") (pintype "input+no_connect"))
    )
  )
)
